# l1.net
KiCad netlist of a schematic drawn in Altium Designer
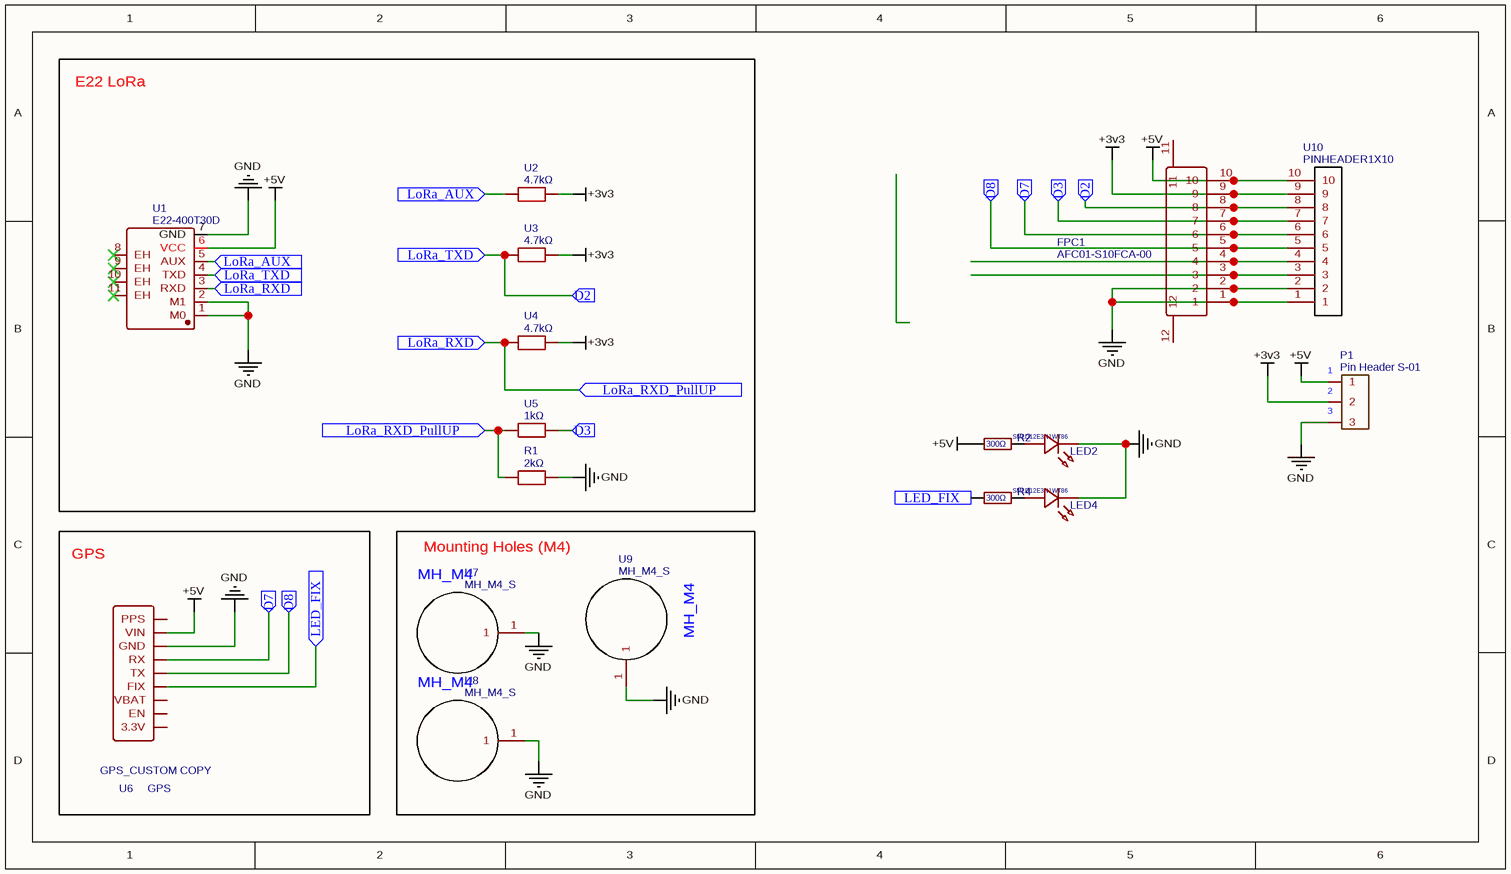
[diagram p0: l1.schdoc]

(export (version "E")
  (design (tool "Eeschema 10.0.6"))
  (components
    (comp (ref "FPC1")
      (value "AFC01-S10FCA-00")
      (fields (field (name "MANUFACTURER") "JS(钜硕电子)") (field (name "CONTRIBUTOR") "LCSC"))
      (libsource (lib "altium-import") (part "root_2_AFC01-S10FCA-00_"))
    )
    (comp (ref "LED2")
      (value "SMLD12E3N1WT86")
      (fields (field (name "MANUFACTURER") "ROHM(罗姆)") (field (name "CONTRIBUTOR") "lcsc"))
      (libsource (lib "altium-import") (part "root_2_SMLD12E3N1WT86_"))
    )
    (comp (ref "LED4")
      (value "SMLD12E3N1WT86")
      (fields (field (name "MANUFACTURER") "ROHM(罗姆)") (field (name "CONTRIBUTOR") "lcsc"))
      (libsource (lib "altium-import") (part "root_2_SMLD12E3N1WT86_"))
    )
    (comp (ref "P1")
      (value "Pin Header S-01")
      (fields
        (field (name "MANUFACTURER") "BOOMELE")
        (field (name "MANUFACTURER PART") "Female headerHDR1X8-2.54")
        (field (name "CONTRIBUTOR") "blackhassio")
      )
      (libsource (lib "altium-import") (part "root_2_Pin Header S-01_"))
    )
    (comp (ref "R1")
      (value "2kΩ")
      (fields
        (field (name "MANUFACTURER") "VO(翔胜)")
        (field (name "MANUFACTURER PART") "SCR0603F2K")
        (field (name "CONTRIBUTOR") "lcsc")
      )
      (libsource (lib "altium-import") (part "root_0_2kΩ_"))
    )
    (comp (ref "R2")
      (value "300Ω")
      (fields
        (field (name "MANUFACTURER") "UNI-ROYAL(厚声)")
        (field (name "MANUFACTURER PART") "1206W4J0301T5E")
      )
      (libsource (lib "altium-import") (part "root_0_300Ω_"))
    )
    (comp (ref "R4")
      (value "300Ω")
      (fields
        (field (name "MANUFACTURER") "UNI-ROYAL(厚声)")
        (field (name "MANUFACTURER PART") "1206W4J0301T5E")
      )
      (libsource (lib "altium-import") (part "root_0_300Ω_"))
    )
    (comp (ref "U1")
      (value "E22-400T30D")
      (fields (field (name "MANUFACTURER") "EBYTE(亿佰特)") (field (name "CONTRIBUTOR") "lcsc"))
      (libsource (lib "altium-import") (part "root_2_E22-400T30D_"))
    )
    (comp (ref "U2")
      (value "4.7kΩ")
      (fields
        (field (name "MANUFACTURER") "FOJAN(富捷)")
        (field (name "MANUFACTURER PART") "FRC1206J472 TS")
        (field (name "CONTRIBUTOR") "lcsc")
      )
      (libsource (lib "altium-import") (part "root_0_4.7kΩ_"))
    )
    (comp (ref "U3")
      (value "4.7kΩ")
      (fields
        (field (name "MANUFACTURER") "FOJAN(富捷)")
        (field (name "MANUFACTURER PART") "FRC1206J472 TS")
        (field (name "CONTRIBUTOR") "lcsc")
      )
      (libsource (lib "altium-import") (part "root_0_4.7kΩ_"))
    )
    (comp (ref "U4")
      (value "4.7kΩ")
      (fields
        (field (name "MANUFACTURER") "FOJAN(富捷)")
        (field (name "MANUFACTURER PART") "FRC1206J472 TS")
        (field (name "CONTRIBUTOR") "lcsc")
      )
      (libsource (lib "altium-import") (part "root_0_4.7kΩ_"))
    )
    (comp (ref "U5")
      (value "1kΩ")
      (fields
        (field (name "MANUFACTURER") "FH(风华)")
        (field (name "MANUFACTURER PART") "TC02G1001FT")
        (field (name "CONTRIBUTOR") "lcsc")
      )
      (libsource (lib "altium-import") (part "root_0_1kΩ_"))
    )
    (comp (ref "U6")
      (value "GPS_CUSTOM COPY")
      (fields (field (name "CONTRIBUTOR") "swnotjoao"))
      (libsource (lib "altium-import") (part "root_2_GPS_CUSTOM COPY_"))
    )
    (comp (ref "U7")
      (value "MH_M4_S")
      (fields (field (name "CONTRIBUTOR") "js314dev"))
      (libsource (lib "altium-import") (part "root_0_MH_M4_S_"))
    )
    (comp (ref "U8")
      (value "MH_M4_S")
      (fields (field (name "CONTRIBUTOR") "js314dev"))
      (libsource (lib "altium-import") (part "root_0_MH_M4_S_"))
    )
    (comp (ref "U9")
      (value "MH_M4_S")
      (fields (field (name "CONTRIBUTOR") "js314dev"))
      (libsource (lib "altium-import") (part "root_3_MH_M4_S_"))
    )
    (comp (ref "U10")
      (value "PINHEADER1X10")
      (fields (field (name "CONTRIBUTOR") "sorza102"))
      (libsource (lib "altium-import") (part "root_2_PINHEADER1X10_"))
    )
  )
  (nets
    (net (code "1") (name "+3v3") (class "Default")
      (node (ref "FPC1") (pin "9") (pinfunction "9_9") (pintype "passive"))
      (node (ref "P1") (pin "2") (pinfunction "2_2") (pintype "passive"))
      (node (ref "U10") (pin "9") (pinfunction "9_9") (pintype "passive"))
      (node (ref "U2") (pin "2") (pinfunction "2_2") (pintype "passive"))
      (node (ref "U3") (pin "2") (pinfunction "2_2") (pintype "passive"))
      (node (ref "U4") (pin "2") (pinfunction "2_2") (pintype "passive"))
    )
    (net (code "2") (name "+5V") (class "Default")
      (node (ref "FPC1") (pin "10") (pinfunction "10_10") (pintype "passive"))
      (node (ref "P1") (pin "1") (pinfunction "1_1") (pintype "passive"))
      (node (ref "R2") (pin "1") (pinfunction "1_1") (pintype "passive"))
      (node (ref "U1") (pin "6") (pinfunction "VCC_6") (pintype "passive"))
      (node (ref "U10") (pin "10") (pinfunction "10_10") (pintype "passive"))
      (node (ref "U6") (pin "8") (pinfunction "VIN_8") (pintype "passive"))
    )
    (net (code "3") (name "/D2") (class "Default")
      (node (ref "FPC1") (pin "8") (pinfunction "8_8") (pintype "passive"))
      (node (ref "U1") (pin "4") (pinfunction "TXD_4") (pintype "passive"))
      (node (ref "U10") (pin "8") (pinfunction "8_8") (pintype "passive"))
      (node (ref "U3") (pin "1") (pinfunction "1_1") (pintype "passive"))
    )
    (net (code "4") (name "/D3") (class "Default")
      (node (ref "FPC1") (pin "7") (pinfunction "7_7") (pintype "passive"))
      (node (ref "U10") (pin "7") (pinfunction "7_7") (pintype "passive"))
      (node (ref "U5") (pin "2") (pinfunction "2_2") (pintype "passive"))
    )
    (net (code "5") (name "/D7") (class "Default")
      (node (ref "FPC1") (pin "6") (pinfunction "6_6") (pintype "passive"))
      (node (ref "U10") (pin "6") (pinfunction "6_6") (pintype "passive"))
      (node (ref "U6") (pin "6") (pinfunction "RX_6") (pintype "passive"))
    )
    (net (code "6") (name "/D8") (class "Default")
      (node (ref "FPC1") (pin "5") (pinfunction "5_5") (pintype "passive"))
      (node (ref "U10") (pin "5") (pinfunction "5_5") (pintype "passive"))
      (node (ref "U6") (pin "5") (pinfunction "TX_5") (pintype "passive"))
    )
    (net (code "7") (name "/LED_FIX") (class "Default")
      (node (ref "R4") (pin "1") (pinfunction "1_1") (pintype "passive"))
      (node (ref "U6") (pin "4") (pinfunction "FIX_4") (pintype "passive"))
    )
    (net (code "8") (name "/LoRa_AUX") (class "Default")
      (node (ref "U1") (pin "5") (pinfunction "AUX_5") (pintype "passive"))
      (node (ref "U2") (pin "1") (pinfunction "1_1") (pintype "passive"))
    )
    (net (code "9") (name "/LoRa_RXD") (class "Default")
      (node (ref "R1") (pin "1") (pinfunction "1_1") (pintype "passive"))
      (node (ref "U1") (pin "3") (pinfunction "RXD_3") (pintype "passive"))
      (node (ref "U4") (pin "1") (pinfunction "1_1") (pintype "passive"))
      (node (ref "U5") (pin "1") (pinfunction "1_1") (pintype "passive"))
    )
    (net (code "10") (name "GND") (class "Default")
      (node (ref "FPC1") (pin "1") (pinfunction "1_1") (pintype "passive"))
      (node (ref "FPC1") (pin "2") (pinfunction "2_2") (pintype "passive"))
      (node (ref "LED2") (pin "1") (pinfunction "-_1") (pintype "passive"))
      (node (ref "LED4") (pin "1") (pinfunction "-_1") (pintype "passive"))
      (node (ref "P1") (pin "3") (pinfunction "3_3") (pintype "passive"))
      (node (ref "R1") (pin "2") (pinfunction "2_2") (pintype "passive"))
      (node (ref "U1") (pin "1") (pinfunction "M0_1") (pintype "passive"))
      (node (ref "U1") (pin "2") (pinfunction "M1_2") (pintype "passive"))
      (node (ref "U1") (pin "7") (pinfunction "GND_7") (pintype "passive"))
      (node (ref "U10") (pin "1") (pinfunction "1_1") (pintype "passive"))
      (node (ref "U10") (pin "2") (pinfunction "2_2") (pintype "passive"))
      (node (ref "U6") (pin "7") (pinfunction "GND_7") (pintype "passive"))
      (node (ref "U7") (pin "1") (pinfunction "1_1") (pintype "passive"))
      (node (ref "U8") (pin "1") (pinfunction "1_1") (pintype "passive"))
      (node (ref "U9") (pin "1") (pinfunction "1_1") (pintype "passive"))
    )
    (net (code "11") (name "Net-(FPC1-Pad3)") (class "Default")
      (node (ref "FPC1") (pin "3") (pinfunction "3_3") (pintype "passive"))
      (node (ref "U10") (pin "3") (pinfunction "3_3") (pintype "passive"))
    )
    (net (code "12") (name "Net-(FPC1-Pad4)") (class "Default")
      (node (ref "FPC1") (pin "4") (pinfunction "4_4") (pintype "passive"))
      (node (ref "U10") (pin "4") (pinfunction "4_4") (pintype "passive"))
    )
    (net (code "13") (name "Net-(LED2-+)") (class "Default")
      (node (ref "LED2") (pin "2") (pinfunction "+_2") (pintype "passive"))
      (node (ref "R2") (pin "2") (pinfunction "2_2") (pintype "passive"))
    )
    (net (code "14") (name "Net-(LED4-+)") (class "Default")
      (node (ref "LED4") (pin "2") (pinfunction "+_2") (pintype "passive"))
      (node (ref "R4") (pin "2") (pinfunction "2_2") (pintype "passive"))
    )
    (net (code "15") (name "unconnected-(FPC1-Pad11)") (class "Default")
      (node (ref "FPC1") (pin "11") (pinfunction "11_11") (pintype "passive"))
    )
    (net (code "16") (name "unconnected-(FPC1-Pad12)") (class "Default")
      (node (ref "FPC1") (pin "12") (pinfunction "12_12") (pintype "passive"))
    )
    (net (code "17") (name "unconnected-(U1-EH-Pad8)") (class "Default")
      (node (ref "U1") (pin "8") (pinfunction "EH_8") (pintype "passive+no_connect"))
    )
    (net (code "18") (name "unconnected-(U1-EH-Pad9)") (class "Default")
      (node (ref "U1") (pin "9") (pinfunction "EH_9") (pintype "passive+no_connect"))
    )
    (net (code "19") (name "unconnected-(U1-EH-Pad10)") (class "Default")
      (node (ref "U1") (pin "10") (pinfunction "EH_10") (pintype "passive+no_connect"))
    )
    (net (code "20") (name "unconnected-(U1-EH-Pad11)") (class "Default")
      (node (ref "U1") (pin "11") (pinfunction "EH_11") (pintype "passive+no_connect"))
    )
    (net (code "21") (name "unconnected-(U6-3.3V-Pad1)") (class "Default")
      (node (ref "U6") (pin "1") (pinfunction "3.3V_1") (pintype "passive"))
    )
    (net (code "22") (name "unconnected-(U6-EN-Pad2)") (class "Default")
      (node (ref "U6") (pin "2") (pinfunction "EN_2") (pintype "passive"))
    )
    (net (code "23") (name "unconnected-(U6-PPS-Pad9)") (class "Default")
      (node (ref "U6") (pin "9") (pinfunction "PPS_9") (pintype "passive"))
    )
    (net (code "24") (name "unconnected-(U6-VBAT-Pad3)") (class "Default")
      (node (ref "U6") (pin "3") (pinfunction "VBAT_3") (pintype "passive"))
    )
  )
)
